# Input.net
KiCad netlist of a schematic drawn in EAGLE
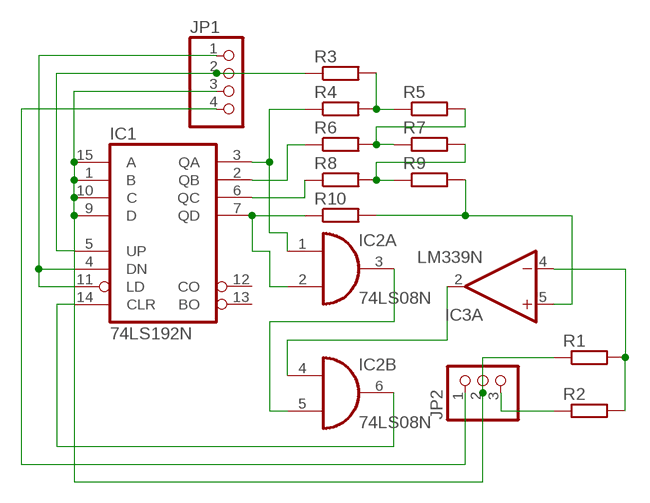
[diagram p0: schematic, sheet 1]

(export (version "E")
  (design (tool "Eeschema 10.0.6"))
  (components
    (comp (ref "IC1")
      (value "74LS192N")
      (footprint "eagle-import:DIL16")
      (libsource (lib "eagle-import") (part "74192NLS"))
    )
    (comp (ref "IC2")
      (value "74LS08N")
      (footprint "eagle-import:DIL14")
      (libsource (lib "eagle-import") (part "7408NLS"))
    )
    (comp (ref "IC3")
      (value "LM339N")
      (footprint "eagle-import:DIL14")
      (libsource (lib "eagle-import") (part "LM339N"))
    )
    (comp (ref "JP1")
      (value "PINHD-1X4")
      (footprint "eagle-import:1X04")
      (libsource (lib "eagle-import") (part "PINHD-1X4"))
    )
    (comp (ref "JP2")
      (value "PINHD-1X3")
      (footprint "eagle-import:1X03")
      (libsource (lib "eagle-import") (part "PINHD-1X3"))
    )
    (comp (ref "R1")
      (value "R-EU_0207/10")
      (footprint "eagle-import:0207_10")
      (libsource (lib "eagle-import") (part "R-EU_0207/10"))
    )
    (comp (ref "R2")
      (value "R-EU_0207/10")
      (footprint "eagle-import:0207_10")
      (libsource (lib "eagle-import") (part "R-EU_0207/10"))
    )
    (comp (ref "R3")
      (value "R-EU_0207/10")
      (footprint "eagle-import:0207_10")
      (libsource (lib "eagle-import") (part "R-EU_0207/10"))
    )
    (comp (ref "R4")
      (value "R-EU_0207/10")
      (footprint "eagle-import:0207_10")
      (libsource (lib "eagle-import") (part "R-EU_0207/10"))
    )
    (comp (ref "R5")
      (value "R-EU_0207/10")
      (footprint "eagle-import:0207_10")
      (libsource (lib "eagle-import") (part "R-EU_0207/10"))
    )
    (comp (ref "R6")
      (value "R-EU_0207/10")
      (footprint "eagle-import:0207_10")
      (libsource (lib "eagle-import") (part "R-EU_0207/10"))
    )
    (comp (ref "R7")
      (value "R-EU_0207/10")
      (footprint "eagle-import:0207_10")
      (libsource (lib "eagle-import") (part "R-EU_0207/10"))
    )
    (comp (ref "R8")
      (value "R-EU_0207/10")
      (footprint "eagle-import:0207_10")
      (libsource (lib "eagle-import") (part "R-EU_0207/10"))
    )
    (comp (ref "R9")
      (value "R-EU_0207/10")
      (footprint "eagle-import:0207_10")
      (libsource (lib "eagle-import") (part "R-EU_0207/10"))
    )
    (comp (ref "R10")
      (value "R-EU_0207/10")
      (footprint "eagle-import:0207_10")
      (libsource (lib "eagle-import") (part "R-EU_0207/10"))
    )
  )
  (nets
    (net (code "1") (name "Net-(IC1A-A)") (class "Default")
      (node (ref "IC1") (pin "1") (pinfunction "B_1") (pintype "input"))
      (node (ref "IC1") (pin "10") (pinfunction "C_10") (pintype "input"))
      (node (ref "IC1") (pin "15") (pinfunction "A_15") (pintype "input"))
      (node (ref "IC1") (pin "9") (pinfunction "D_9") (pintype "input"))
      (node (ref "JP1") (pin "3") (pinfunction "3_3") (pintype "passive"))
      (node (ref "JP2") (pin "2") (pinfunction "2_2") (pintype "passive"))
      (node (ref "R1") (pin "1") (pinfunction "1_1") (pintype "passive"))
    )
    (net (code "2") (name "Net-(IC1A-CLR)") (class "Default")
      (node (ref "IC1") (pin "14") (pinfunction "CLR_14") (pintype "input"))
      (node (ref "IC2") (pin "6") (pinfunction "O_6") (pintype "output"))
    )
    (net (code "3") (name "Net-(IC1A-DN)") (class "Default")
      (node (ref "IC1") (pin "11") (pinfunction "LD_11") (pintype "input"))
      (node (ref "IC1") (pin "4") (pinfunction "DN_4") (pintype "input"))
      (node (ref "JP1") (pin "1") (pinfunction "1_1") (pintype "passive"))
    )
    (net (code "4") (name "Net-(IC1A-QA)") (class "Default")
      (node (ref "IC1") (pin "3") (pinfunction "QA_3") (pintype "output"))
      (node (ref "IC2") (pin "1") (pinfunction "I0_1") (pintype "input"))
      (node (ref "R4") (pin "1") (pinfunction "1_1") (pintype "passive"))
    )
    (net (code "5") (name "Net-(IC1A-QB)") (class "Default")
      (node (ref "IC1") (pin "2") (pinfunction "QB_2") (pintype "output"))
      (node (ref "R6") (pin "1") (pinfunction "1_1") (pintype "passive"))
    )
    (net (code "6") (name "Net-(IC1A-QC)") (class "Default")
      (node (ref "IC1") (pin "6") (pinfunction "QC_6") (pintype "output"))
      (node (ref "R8") (pin "1") (pinfunction "1_1") (pintype "passive"))
    )
    (net (code "7") (name "Net-(IC1A-QD)") (class "Default")
      (node (ref "IC1") (pin "7") (pinfunction "QD_7") (pintype "output"))
      (node (ref "IC2") (pin "2") (pinfunction "I1_2") (pintype "input"))
      (node (ref "R10") (pin "1") (pinfunction "1_1") (pintype "passive"))
    )
    (net (code "8") (name "Net-(IC1A-UP)") (class "Default")
      (node (ref "IC1") (pin "5") (pinfunction "UP_5") (pintype "input"))
      (node (ref "JP1") (pin "2") (pinfunction "2_2") (pintype "passive"))
      (node (ref "R3") (pin "1") (pinfunction "1_1") (pintype "passive"))
    )
    (net (code "9") (name "Net-(IC2A-O)") (class "Default")
      (node (ref "IC2") (pin "3") (pinfunction "O_3") (pintype "output"))
      (node (ref "IC2") (pin "5") (pinfunction "I1_5") (pintype "input"))
    )
    (net (code "10") (name "Net-(IC2B-I0)") (class "Default")
      (node (ref "IC2") (pin "4") (pinfunction "I0_4") (pintype "input"))
      (node (ref "IC3") (pin "2") (pinfunction "OUT_2") (pintype "open_collector"))
    )
    (net (code "11") (name "Net-(IC3A-+IN)") (class "Default")
      (node (ref "IC3") (pin "5") (pinfunction "+IN_5") (pintype "input"))
      (node (ref "R10") (pin "2") (pinfunction "2_2") (pintype "passive"))
      (node (ref "R9") (pin "2") (pinfunction "2_2") (pintype "passive"))
    )
    (net (code "12") (name "Net-(IC3A--IN)") (class "Default")
      (node (ref "IC3") (pin "4") (pinfunction "-IN_4") (pintype "input"))
      (node (ref "R1") (pin "2") (pinfunction "2_2") (pintype "passive"))
      (node (ref "R2") (pin "2") (pinfunction "2_2") (pintype "passive"))
    )
    (net (code "13") (name "Net-(JP1-Pad4)") (class "Default")
      (node (ref "JP1") (pin "4") (pinfunction "4_4") (pintype "passive"))
      (node (ref "JP2") (pin "1") (pinfunction "1_1") (pintype "passive"))
    )
    (net (code "14") (name "Net-(JP2-Pad3)") (class "Default")
      (node (ref "JP2") (pin "3") (pinfunction "3_3") (pintype "passive"))
      (node (ref "R2") (pin "1") (pinfunction "1_1") (pintype "passive"))
    )
    (net (code "15") (name "Net-(R3-Pad2)") (class "Default")
      (node (ref "R3") (pin "2") (pinfunction "2_2") (pintype "passive"))
      (node (ref "R4") (pin "2") (pinfunction "2_2") (pintype "passive"))
      (node (ref "R5") (pin "1") (pinfunction "1_1") (pintype "passive"))
    )
    (net (code "16") (name "Net-(R5-Pad2)") (class "Default")
      (node (ref "R5") (pin "2") (pinfunction "2_2") (pintype "passive"))
      (node (ref "R6") (pin "2") (pinfunction "2_2") (pintype "passive"))
      (node (ref "R7") (pin "1") (pinfunction "1_1") (pintype "passive"))
    )
    (net (code "17") (name "Net-(R7-Pad2)") (class "Default")
      (node (ref "R7") (pin "2") (pinfunction "2_2") (pintype "passive"))
      (node (ref "R8") (pin "2") (pinfunction "2_2") (pintype "passive"))
      (node (ref "R9") (pin "1") (pinfunction "1_1") (pintype "passive"))
    )
    (net (code "18") (name "unconnected-(IC1A-BO-Pad13)") (class "Default")
      (node (ref "IC1") (pin "13") (pinfunction "BO_13") (pintype "output"))
    )
    (net (code "19") (name "unconnected-(IC1A-CO-Pad12)") (class "Default")
      (node (ref "IC1") (pin "12") (pinfunction "CO_12") (pintype "output"))
    )
  )
)
